# RF_DAC.net
KiCad netlist of a schematic drawn in Altium Designer
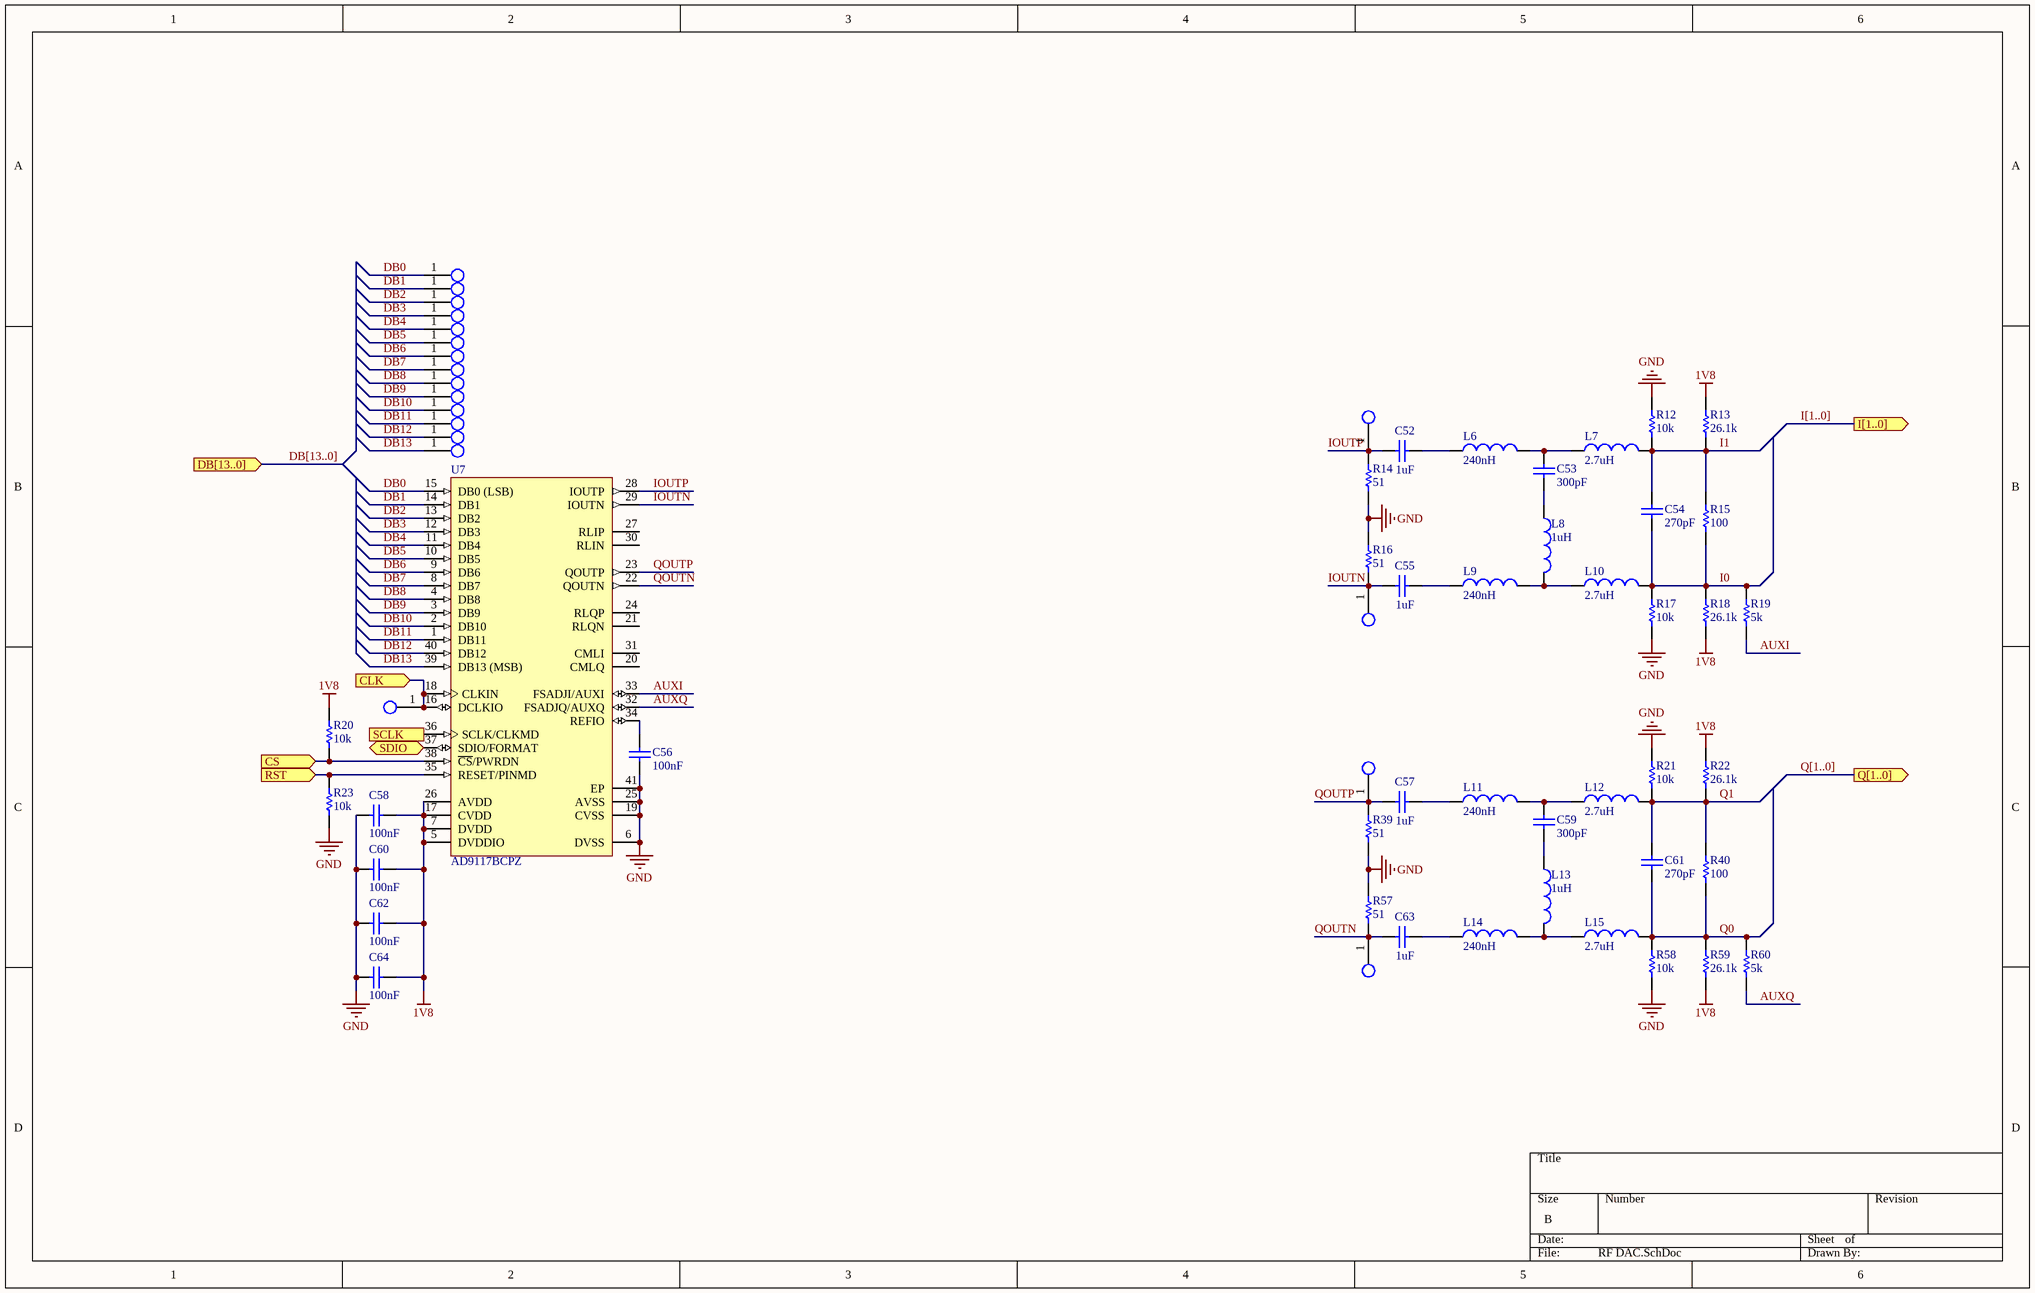
[diagram p0: RF DAC.SchDoc]

(export (version "E")
  (design (tool "Eeschema 10.0.6"))
  (components
    (comp (ref "C52")
      (value "1uF")
      (footprint "1608[0603]")
      (description "Capacitor")
      (fields (field (name "Comment") "Cap") (field (name "PUBLISHER") "Altium Limited"))
      (libsource (lib "Miscellaneous Devices") (part "Cap"))
    )
    (comp (ref "C53")
      (value "300pF")
      (footprint "0402-A")
      (description "Capacitor")
      (fields (field (name "Comment") "Cap") (field (name "PUBLISHER") "Altium Limited"))
      (libsource (lib "Miscellaneous Devices") (part "Cap"))
    )
    (comp (ref "C54")
      (value "270pF")
      (footprint "0402-A")
      (description "Capacitor")
      (fields (field (name "Comment") "Cap") (field (name "PUBLISHER") "Altium Limited"))
      (libsource (lib "Miscellaneous Devices") (part "Cap"))
    )
    (comp (ref "C55")
      (value "1uF")
      (footprint "1608[0603]")
      (description "Capacitor")
      (fields (field (name "Comment") "Cap") (field (name "PUBLISHER") "Altium Limited"))
      (libsource (lib "Miscellaneous Devices") (part "Cap"))
    )
    (comp (ref "C56")
      (value "100nF")
      (footprint "0402-A")
      (description "Capacitor")
      (fields (field (name "Comment") "Cap") (field (name "PUBLISHER") "Altium Limited"))
      (libsource (lib "Miscellaneous Devices") (part "Cap"))
    )
    (comp (ref "C57")
      (value "1uF")
      (footprint "1608[0603]")
      (description "Capacitor")
      (fields (field (name "Comment") "Cap") (field (name "PUBLISHER") "Altium Limited"))
      (libsource (lib "Miscellaneous Devices") (part "Cap"))
    )
    (comp (ref "C58")
      (value "100nF")
      (footprint "0402-A")
      (description "Capacitor")
      (fields (field (name "Comment") "Cap") (field (name "PUBLISHER") "Altium Limited"))
      (libsource (lib "Miscellaneous Devices") (part "Cap"))
    )
    (comp (ref "C59")
      (value "300pF")
      (footprint "0402-A")
      (description "Capacitor")
      (fields (field (name "Comment") "Cap") (field (name "PUBLISHER") "Altium Limited"))
      (libsource (lib "Miscellaneous Devices") (part "Cap"))
    )
    (comp (ref "C60")
      (value "100nF")
      (footprint "0402-A")
      (description "Capacitor")
      (fields (field (name "Comment") "Cap") (field (name "PUBLISHER") "Altium Limited"))
      (libsource (lib "Miscellaneous Devices") (part "Cap"))
    )
    (comp (ref "C61")
      (value "270pF")
      (footprint "0402-A")
      (description "Capacitor")
      (fields (field (name "Comment") "Cap") (field (name "PUBLISHER") "Altium Limited"))
      (libsource (lib "Miscellaneous Devices") (part "Cap"))
    )
    (comp (ref "C62")
      (value "100nF")
      (footprint "0402-A")
      (description "Capacitor")
      (fields (field (name "Comment") "Cap") (field (name "PUBLISHER") "Altium Limited"))
      (libsource (lib "Miscellaneous Devices") (part "Cap"))
    )
    (comp (ref "C63")
      (value "1uF")
      (footprint "1608[0603]")
      (description "Capacitor")
      (fields (field (name "Comment") "Cap") (field (name "PUBLISHER") "Altium Limited"))
      (libsource (lib "Miscellaneous Devices") (part "Cap"))
    )
    (comp (ref "C64")
      (value "100nF")
      (footprint "0402-A")
      (description "Capacitor")
      (fields (field (name "Comment") "Cap") (field (name "PUBLISHER") "Altium Limited"))
      (libsource (lib "Miscellaneous Devices") (part "Cap"))
    )
    (comp (ref "CLK")
      (value "5029")
      (footprint "EXPOSED PAD 0.02X0.02")
      (libsource (lib "5029") (part "5029"))
    )
    (comp (ref "DB0")
      (value "5029")
      (footprint "EXPOSED PAD 0.02X0.02")
      (libsource (lib "5029") (part "5029"))
    )
    (comp (ref "DB1")
      (value "5029")
      (footprint "EXPOSED PAD 0.02X0.02")
      (libsource (lib "5029") (part "5029"))
    )
    (comp (ref "DB2")
      (value "5029")
      (footprint "EXPOSED PAD 0.02X0.02")
      (libsource (lib "5029") (part "5029"))
    )
    (comp (ref "DB3")
      (value "5029")
      (footprint "EXPOSED PAD 0.02X0.02")
      (libsource (lib "5029") (part "5029"))
    )
    (comp (ref "DB4")
      (value "5029")
      (footprint "EXPOSED PAD 0.02X0.02")
      (libsource (lib "5029") (part "5029"))
    )
    (comp (ref "DB5")
      (value "5029")
      (footprint "EXPOSED PAD 0.02X0.02")
      (libsource (lib "5029") (part "5029"))
    )
    (comp (ref "DB6")
      (value "5029")
      (footprint "EXPOSED PAD 0.02X0.02")
      (libsource (lib "5029") (part "5029"))
    )
    (comp (ref "DB7")
      (value "5029")
      (footprint "EXPOSED PAD 0.02X0.02")
      (libsource (lib "5029") (part "5029"))
    )
    (comp (ref "DB8")
      (value "5029")
      (footprint "EXPOSED PAD 0.02X0.02")
      (libsource (lib "5029") (part "5029"))
    )
    (comp (ref "DB9")
      (value "5029")
      (footprint "EXPOSED PAD 0.02X0.02")
      (libsource (lib "5029") (part "5029"))
    )
    (comp (ref "DB10")
      (value "5029")
      (footprint "EXPOSED PAD 0.02X0.02")
      (libsource (lib "5029") (part "5029"))
    )
    (comp (ref "DB11")
      (value "5029")
      (footprint "EXPOSED PAD 0.02X0.02")
      (libsource (lib "5029") (part "5029"))
    )
    (comp (ref "DB12")
      (value "5029")
      (footprint "EXPOSED PAD 0.02X0.02")
      (libsource (lib "5029") (part "5029"))
    )
    (comp (ref "DB13")
      (value "5029")
      (footprint "EXPOSED PAD 0.02X0.02")
      (libsource (lib "5029") (part "5029"))
    )
    (comp (ref "J22")
      (value "5029")
      (footprint "EXPOSED PAD 0.02X0.02")
      (libsource (lib "5029") (part "5029"))
    )
    (comp (ref "J25")
      (value "5029")
      (footprint "EXPOSED PAD 0.02X0.02")
      (libsource (lib "5029") (part "5029"))
    )
    (comp (ref "J26")
      (value "5029")
      (footprint "EXPOSED PAD 0.02X0.02")
      (libsource (lib "5029") (part "5029"))
    )
    (comp (ref "J29")
      (value "5029")
      (footprint "EXPOSED PAD 0.02X0.02")
      (libsource (lib "5029") (part "5029"))
    )
    (comp (ref "L6")
      (value "240nH")
      (footprint "0402-A")
      (description "Inductor")
      (fields (field (name "PUBLISHER") "Altium Limited"))
      (libsource (lib "Miscellaneous Devices") (part "Inductor"))
    )
    (comp (ref "L7")
      (value "2.7uH")
      (footprint "1608[0603]")
      (description "Inductor")
      (fields (field (name "PUBLISHER") "Altium Limited"))
      (libsource (lib "Miscellaneous Devices") (part "Inductor"))
    )
    (comp (ref "L8")
      (value "1uH")
      (footprint "1608[0603]")
      (description "Inductor")
      (fields (field (name "PUBLISHER") "Altium Limited"))
      (libsource (lib "Miscellaneous Devices") (part "Inductor"))
    )
    (comp (ref "L9")
      (value "240nH")
      (footprint "0402-A")
      (description "Inductor")
      (fields (field (name "PUBLISHER") "Altium Limited"))
      (libsource (lib "Miscellaneous Devices") (part "Inductor"))
    )
    (comp (ref "L10")
      (value "2.7uH")
      (footprint "1608[0603]")
      (description "Inductor")
      (fields (field (name "PUBLISHER") "Altium Limited"))
      (libsource (lib "Miscellaneous Devices") (part "Inductor"))
    )
    (comp (ref "L11")
      (value "240nH")
      (footprint "0402-A")
      (description "Inductor")
      (fields (field (name "PUBLISHER") "Altium Limited"))
      (libsource (lib "Miscellaneous Devices") (part "Inductor"))
    )
    (comp (ref "L12")
      (value "2.7uH")
      (footprint "1608[0603]")
      (description "Inductor")
      (fields (field (name "PUBLISHER") "Altium Limited"))
      (libsource (lib "Miscellaneous Devices") (part "Inductor"))
    )
    (comp (ref "L13")
      (value "1uH")
      (footprint "1608[0603]")
      (description "Inductor")
      (fields (field (name "PUBLISHER") "Altium Limited"))
      (libsource (lib "Miscellaneous Devices") (part "Inductor"))
    )
    (comp (ref "L14")
      (value "240nH")
      (footprint "0402-A")
      (description "Inductor")
      (fields (field (name "PUBLISHER") "Altium Limited"))
      (libsource (lib "Miscellaneous Devices") (part "Inductor"))
    )
    (comp (ref "L15")
      (value "2.7uH")
      (footprint "1608[0603]")
      (description "Inductor")
      (fields (field (name "PUBLISHER") "Altium Limited"))
      (libsource (lib "Miscellaneous Devices") (part "Inductor"))
    )
    (comp (ref "R12")
      (value "10k")
      (footprint "0402-A")
      (description "Resistor")
      (fields (field (name "Comment") "Res1") (field (name "PUBLISHER") "Altium Limited"))
      (libsource (lib "Miscellaneous Devices") (part "Res1"))
    )
    (comp (ref "R13")
      (value "26.1k")
      (footprint "0402-A")
      (description "Resistor")
      (fields (field (name "Comment") "Res1") (field (name "PUBLISHER") "Altium Limited"))
      (libsource (lib "Miscellaneous Devices") (part "Res1"))
    )
    (comp (ref "R14")
      (value "51")
      (footprint "0402-A")
      (description "Resistor")
      (fields (field (name "Comment") "Res1") (field (name "PUBLISHER") "Altium Limited"))
      (libsource (lib "Miscellaneous Devices") (part "Res1"))
    )
    (comp (ref "R15")
      (value "100")
      (footprint "0402-A")
      (description "Resistor")
      (fields (field (name "Comment") "Res1") (field (name "PUBLISHER") "Altium Limited"))
      (libsource (lib "Miscellaneous Devices") (part "Res1"))
    )
    (comp (ref "R16")
      (value "51")
      (footprint "0402-A")
      (description "Resistor")
      (fields (field (name "Comment") "Res1") (field (name "PUBLISHER") "Altium Limited"))
      (libsource (lib "Miscellaneous Devices") (part "Res1"))
    )
    (comp (ref "R17")
      (value "10k")
      (footprint "0402-A")
      (description "Resistor")
      (fields (field (name "Comment") "Res1") (field (name "PUBLISHER") "Altium Limited"))
      (libsource (lib "Miscellaneous Devices") (part "Res1"))
    )
    (comp (ref "R18")
      (value "26.1k")
      (footprint "0402-A")
      (description "Resistor")
      (fields (field (name "Comment") "Res1") (field (name "PUBLISHER") "Altium Limited"))
      (libsource (lib "Miscellaneous Devices") (part "Res1"))
    )
    (comp (ref "R19")
      (value "5k")
      (footprint "0402-A")
      (description "Resistor")
      (fields (field (name "Comment") "Res1") (field (name "PUBLISHER") "Altium Limited"))
      (libsource (lib "Miscellaneous Devices") (part "Res1"))
    )
    (comp (ref "R20")
      (value "10k")
      (footprint "0402-A")
      (description "Resistor")
      (fields (field (name "Comment") "Res1") (field (name "PUBLISHER") "Altium Limited"))
      (libsource (lib "Miscellaneous Devices") (part "Res1"))
    )
    (comp (ref "R21")
      (value "10k")
      (footprint "0402-A")
      (description "Resistor")
      (fields (field (name "Comment") "Res1") (field (name "PUBLISHER") "Altium Limited"))
      (libsource (lib "Miscellaneous Devices") (part "Res1"))
    )
    (comp (ref "R22")
      (value "26.1k")
      (footprint "0402-A")
      (description "Resistor")
      (fields (field (name "Comment") "Res1") (field (name "PUBLISHER") "Altium Limited"))
      (libsource (lib "Miscellaneous Devices") (part "Res1"))
    )
    (comp (ref "R23")
      (value "10k")
      (footprint "0402-A")
      (description "Resistor")
      (fields (field (name "Comment") "Res1") (field (name "PUBLISHER") "Altium Limited"))
      (libsource (lib "Miscellaneous Devices") (part "Res1"))
    )
    (comp (ref "R39")
      (value "51")
      (footprint "0402-A")
      (description "Resistor")
      (fields (field (name "Comment") "Res1") (field (name "PUBLISHER") "Altium Limited"))
      (libsource (lib "Miscellaneous Devices") (part "Res1"))
    )
    (comp (ref "R40")
      (value "100")
      (footprint "0402-A")
      (description "Resistor")
      (fields (field (name "Comment") "Res1") (field (name "PUBLISHER") "Altium Limited"))
      (libsource (lib "Miscellaneous Devices") (part "Res1"))
    )
    (comp (ref "R57")
      (value "51")
      (footprint "0402-A")
      (description "Resistor")
      (fields (field (name "Comment") "Res1") (field (name "PUBLISHER") "Altium Limited"))
      (libsource (lib "Miscellaneous Devices") (part "Res1"))
    )
    (comp (ref "R58")
      (value "10k")
      (footprint "0402-A")
      (description "Resistor")
      (fields (field (name "Comment") "Res1") (field (name "PUBLISHER") "Altium Limited"))
      (libsource (lib "Miscellaneous Devices") (part "Res1"))
    )
    (comp (ref "R59")
      (value "26.1k")
      (footprint "0402-A")
      (description "Resistor")
      (fields (field (name "Comment") "Res1") (field (name "PUBLISHER") "Altium Limited"))
      (libsource (lib "Miscellaneous Devices") (part "Res1"))
    )
    (comp (ref "R60")
      (value "5k")
      (footprint "0402-A")
      (description "Resistor")
      (fields (field (name "Comment") "Res1") (field (name "PUBLISHER") "Altium Limited"))
      (libsource (lib "Miscellaneous Devices") (part "Res1"))
    )
    (comp (ref "U7")
      (value "AD9117BCPZ")
      (footprint "CP-40-1_N")
      (description "Dual 14-Bit Low Power TxDAC Digital-to-Analog Converter, 0 to +70 degC, CP-40-1, Pb-Free, Tray")
      (fields (field (name "MANUFACTURER") "Analog Devices") (field (name "GENERIC PART NUMBER") "AD9117"))
      (libsource (lib "Altium Content Vault") (part "ADI-AD9117-CP-40-1"))
    )
  )
  (nets
    (net (code "1") (name "/AUXI") (class "Default")
      (node (ref "R19") (pin "1") (pinfunction "1_1") (pintype "passive"))
      (node (ref "U7") (pin "33") (pinfunction "FSADJI/AUXI_33") (pintype "bidirectional"))
    )
    (net (code "2") (name "/AUXQ") (class "Default")
      (node (ref "R60") (pin "1") (pinfunction "1_1") (pintype "passive"))
      (node (ref "U7") (pin "32") (pinfunction "FSADJQ/AUXQ_32") (pintype "bidirectional"))
    )
    (net (code "3") (name "/CLK") (class "Default")
      (node (ref "CLK") (pin "1") (pintype "passive"))
      (node (ref "U7") (pin "16") (pinfunction "DCLKIO_16") (pintype "bidirectional"))
      (node (ref "U7") (pin "18") (pinfunction "CLKIN_18") (pintype "input"))
    )
    (net (code "4") (name "/CS") (class "Default")
      (node (ref "R20") (pin "1") (pinfunction "1_1") (pintype "passive"))
      (node (ref "U7") (pin "38") (pinfunction "~{CS}/PWRDN_38") (pintype "input"))
    )
    (net (code "5") (name "/DB0") (class "Default")
      (node (ref "DB0") (pin "1") (pintype "passive"))
      (node (ref "U7") (pin "15") (pinfunction "DB0_(LSB)_15") (pintype "input"))
    )
    (net (code "6") (name "/DB1") (class "Default")
      (node (ref "DB1") (pin "1") (pintype "passive"))
      (node (ref "U7") (pin "14") (pinfunction "DB1_14") (pintype "input"))
    )
    (net (code "7") (name "/DB2") (class "Default")
      (node (ref "DB2") (pin "1") (pintype "passive"))
      (node (ref "U7") (pin "13") (pinfunction "DB2_13") (pintype "input"))
    )
    (net (code "8") (name "/DB3") (class "Default")
      (node (ref "DB3") (pin "1") (pintype "passive"))
      (node (ref "U7") (pin "12") (pinfunction "DB3_12") (pintype "input"))
    )
    (net (code "9") (name "/DB4") (class "Default")
      (node (ref "DB4") (pin "1") (pintype "passive"))
      (node (ref "U7") (pin "11") (pinfunction "DB4_11") (pintype "input"))
    )
    (net (code "10") (name "/DB5") (class "Default")
      (node (ref "DB5") (pin "1") (pintype "passive"))
      (node (ref "U7") (pin "10") (pinfunction "DB5_10") (pintype "input"))
    )
    (net (code "11") (name "/DB6") (class "Default")
      (node (ref "DB6") (pin "1") (pintype "passive"))
      (node (ref "U7") (pin "9") (pinfunction "DB6_9") (pintype "input"))
    )
    (net (code "12") (name "/DB7") (class "Default")
      (node (ref "DB7") (pin "1") (pintype "passive"))
      (node (ref "U7") (pin "8") (pinfunction "DB7_8") (pintype "input"))
    )
    (net (code "13") (name "/DB8") (class "Default")
      (node (ref "DB8") (pin "1") (pintype "passive"))
      (node (ref "U7") (pin "4") (pinfunction "DB8_4") (pintype "input"))
    )
    (net (code "14") (name "/DB9") (class "Default")
      (node (ref "DB9") (pin "1") (pintype "passive"))
      (node (ref "U7") (pin "3") (pinfunction "DB9_3") (pintype "input"))
    )
    (net (code "15") (name "/DB10") (class "Default")
      (node (ref "DB10") (pin "1") (pintype "passive"))
      (node (ref "U7") (pin "2") (pinfunction "DB10_2") (pintype "input"))
    )
    (net (code "16") (name "/DB11") (class "Default")
      (node (ref "DB11") (pin "1") (pintype "passive"))
      (node (ref "U7") (pin "1") (pinfunction "DB11_1") (pintype "input"))
    )
    (net (code "17") (name "/DB12") (class "Default")
      (node (ref "DB12") (pin "1") (pintype "passive"))
      (node (ref "U7") (pin "40") (pinfunction "DB12_40") (pintype "input"))
    )
    (net (code "18") (name "/DB13") (class "Default")
      (node (ref "DB13") (pin "1") (pintype "passive"))
      (node (ref "U7") (pin "39") (pinfunction "DB13_(MSB)_39") (pintype "input"))
    )
    (net (code "20") (name "/I0") (class "Default")
      (node (ref "C54") (pin "2") (pinfunction "2_2") (pintype "passive"))
      (node (ref "L10") (pin "2") (pinfunction "2_2") (pintype "passive"))
      (node (ref "R15") (pin "1") (pinfunction "1_1") (pintype "passive"))
      (node (ref "R17") (pin "2") (pinfunction "2_2") (pintype "passive"))
      (node (ref "R18") (pin "2") (pinfunction "2_2") (pintype "passive"))
      (node (ref "R19") (pin "2") (pinfunction "2_2") (pintype "passive"))
    )
    (net (code "21") (name "/I1") (class "Default")
      (node (ref "C54") (pin "1") (pinfunction "1_1") (pintype "passive"))
      (node (ref "L7") (pin "2") (pinfunction "2_2") (pintype "passive"))
      (node (ref "R12") (pin "1") (pinfunction "1_1") (pintype "passive"))
      (node (ref "R13") (pin "1") (pinfunction "1_1") (pintype "passive"))
      (node (ref "R15") (pin "2") (pinfunction "2_2") (pintype "passive"))
    )
    (net (code "22") (name "/IOUTN") (class "Default")
      (node (ref "C55") (pin "2") (pinfunction "2_2") (pintype "passive"))
      (node (ref "J25") (pin "1") (pintype "passive"))
      (node (ref "R16") (pin "1") (pinfunction "1_1") (pintype "passive"))
      (node (ref "U7") (pin "29") (pinfunction "IOUTN_29") (pintype "output"))
    )
    (net (code "23") (name "/IOUTP") (class "Default")
      (node (ref "C52") (pin "2") (pinfunction "2_2") (pintype "passive"))
      (node (ref "J22") (pin "1") (pintype "passive"))
      (node (ref "R14") (pin "2") (pinfunction "2_2") (pintype "passive"))
      (node (ref "U7") (pin "28") (pinfunction "IOUTP_28") (pintype "output"))
    )
    (net (code "25") (name "/Q0") (class "Default")
      (node (ref "C61") (pin "2") (pinfunction "2_2") (pintype "passive"))
      (node (ref "L15") (pin "2") (pinfunction "2_2") (pintype "passive"))
      (node (ref "R40") (pin "1") (pinfunction "1_1") (pintype "passive"))
      (node (ref "R58") (pin "2") (pinfunction "2_2") (pintype "passive"))
      (node (ref "R59") (pin "2") (pinfunction "2_2") (pintype "passive"))
      (node (ref "R60") (pin "2") (pinfunction "2_2") (pintype "passive"))
    )
    (net (code "26") (name "/Q1") (class "Default")
      (node (ref "C61") (pin "1") (pinfunction "1_1") (pintype "passive"))
      (node (ref "L12") (pin "2") (pinfunction "2_2") (pintype "passive"))
      (node (ref "R21") (pin "1") (pinfunction "1_1") (pintype "passive"))
      (node (ref "R22") (pin "1") (pinfunction "1_1") (pintype "passive"))
      (node (ref "R40") (pin "2") (pinfunction "2_2") (pintype "passive"))
    )
    (net (code "27") (name "/QOUTN") (class "Default")
      (node (ref "C63") (pin "2") (pinfunction "2_2") (pintype "passive"))
      (node (ref "J29") (pin "1") (pintype "passive"))
      (node (ref "R57") (pin "1") (pinfunction "1_1") (pintype "passive"))
      (node (ref "U7") (pin "22") (pinfunction "QOUTN_22") (pintype "output"))
    )
    (net (code "28") (name "/QOUTP") (class "Default")
      (node (ref "C57") (pin "2") (pinfunction "2_2") (pintype "passive"))
      (node (ref "J26") (pin "1") (pintype "passive"))
      (node (ref "R39") (pin "2") (pinfunction "2_2") (pintype "passive"))
      (node (ref "U7") (pin "23") (pinfunction "QOUTP_23") (pintype "output"))
    )
    (net (code "30") (name "/RST") (class "Default")
      (node (ref "R23") (pin "2") (pinfunction "2_2") (pintype "passive"))
      (node (ref "U7") (pin "35") (pinfunction "RESET/PINMD_35") (pintype "input"))
    )
    (net (code "31") (name "/SCLK") (class "Default")
      (node (ref "U7") (pin "36") (pinfunction "SCLK/CLKMD_36") (pintype "input"))
    )
    (net (code "32") (name "/SDIO") (class "Default")
      (node (ref "U7") (pin "37") (pinfunction "SDIO/FORMAT_37") (pintype "bidirectional"))
    )
    (net (code "33") (name "1V8") (class "Default")
      (node (ref "C58") (pin "2") (pinfunction "2_2") (pintype "passive"))
      (node (ref "C60") (pin "2") (pinfunction "2_2") (pintype "passive"))
      (node (ref "C62") (pin "2") (pinfunction "2_2") (pintype "passive"))
      (node (ref "C64") (pin "2") (pinfunction "2_2") (pintype "passive"))
      (node (ref "R13") (pin "2") (pinfunction "2_2") (pintype "passive"))
      (node (ref "R18") (pin "1") (pinfunction "1_1") (pintype "passive"))
      (node (ref "R20") (pin "2") (pinfunction "2_2") (pintype "passive"))
      (node (ref "R22") (pin "2") (pinfunction "2_2") (pintype "passive"))
      (node (ref "R59") (pin "1") (pinfunction "1_1") (pintype "passive"))
      (node (ref "U7") (pin "17") (pinfunction "CVDD_17") (pintype "power_in"))
      (node (ref "U7") (pin "26") (pinfunction "AVDD_26") (pintype "power_in"))
      (node (ref "U7") (pin "5") (pinfunction "DVDDIO_5") (pintype "power_in"))
      (node (ref "U7") (pin "7") (pinfunction "DVDD_7") (pintype "power_in"))
    )
    (net (code "34") (name "GND") (class "Default")
      (node (ref "C56") (pin "1") (pinfunction "1_1") (pintype "passive"))
      (node (ref "C58") (pin "1") (pinfunction "1_1") (pintype "passive"))
      (node (ref "C60") (pin "1") (pinfunction "1_1") (pintype "passive"))
      (node (ref "C62") (pin "1") (pinfunction "1_1") (pintype "passive"))
      (node (ref "C64") (pin "1") (pinfunction "1_1") (pintype "passive"))
      (node (ref "R12") (pin "2") (pinfunction "2_2") (pintype "passive"))
      (node (ref "R14") (pin "1") (pinfunction "1_1") (pintype "passive"))
      (node (ref "R16") (pin "2") (pinfunction "2_2") (pintype "passive"))
      (node (ref "R17") (pin "1") (pinfunction "1_1") (pintype "passive"))
      (node (ref "R21") (pin "2") (pinfunction "2_2") (pintype "passive"))
      (node (ref "R23") (pin "1") (pinfunction "1_1") (pintype "passive"))
      (node (ref "R39") (pin "1") (pinfunction "1_1") (pintype "passive"))
      (node (ref "R57") (pin "2") (pinfunction "2_2") (pintype "passive"))
      (node (ref "R58") (pin "1") (pinfunction "1_1") (pintype "passive"))
      (node (ref "U7") (pin "19") (pinfunction "CVSS_19") (pintype "power_in"))
      (node (ref "U7") (pin "25") (pinfunction "AVSS_25") (pintype "power_in"))
      (node (ref "U7") (pin "41") (pinfunction "EP_41") (pintype "power_in"))
      (node (ref "U7") (pin "6") (pinfunction "DVSS_6") (pintype "power_in"))
    )
    (net (code "35") (name "Net-(C52-Pad1)") (class "Default")
      (node (ref "C52") (pin "1") (pinfunction "1_1") (pintype "passive"))
      (node (ref "L6") (pin "1") (pinfunction "1_1") (pintype "passive"))
    )
    (net (code "36") (name "Net-(C53-Pad1)") (class "Default")
      (node (ref "C53") (pin "1") (pinfunction "1_1") (pintype "passive"))
      (node (ref "L6") (pin "2") (pinfunction "2_2") (pintype "passive"))
      (node (ref "L7") (pin "1") (pinfunction "1_1") (pintype "passive"))
    )
    (net (code "37") (name "Net-(C53-Pad2)") (class "Default")
      (node (ref "C53") (pin "2") (pinfunction "2_2") (pintype "passive"))
      (node (ref "L8") (pin "1") (pinfunction "1_1") (pintype "passive"))
    )
    (net (code "38") (name "Net-(C55-Pad1)") (class "Default")
      (node (ref "C55") (pin "1") (pinfunction "1_1") (pintype "passive"))
      (node (ref "L9") (pin "1") (pinfunction "1_1") (pintype "passive"))
    )
    (net (code "39") (name "Net-(C57-Pad1)") (class "Default")
      (node (ref "C57") (pin "1") (pinfunction "1_1") (pintype "passive"))
      (node (ref "L11") (pin "1") (pinfunction "1_1") (pintype "passive"))
    )
    (net (code "40") (name "Net-(C59-Pad1)") (class "Default")
      (node (ref "C59") (pin "1") (pinfunction "1_1") (pintype "passive"))
      (node (ref "L11") (pin "2") (pinfunction "2_2") (pintype "passive"))
      (node (ref "L12") (pin "1") (pinfunction "1_1") (pintype "passive"))
    )
    (net (code "41") (name "Net-(C59-Pad2)") (class "Default")
      (node (ref "C59") (pin "2") (pinfunction "2_2") (pintype "passive"))
      (node (ref "L13") (pin "1") (pinfunction "1_1") (pintype "passive"))
    )
    (net (code "42") (name "Net-(C63-Pad1)") (class "Default")
      (node (ref "C63") (pin "1") (pinfunction "1_1") (pintype "passive"))
      (node (ref "L14") (pin "1") (pinfunction "1_1") (pintype "passive"))
    )
    (net (code "43") (name "Net-(L10-Pad1)") (class "Default")
      (node (ref "L10") (pin "1") (pinfunction "1_1") (pintype "passive"))
      (node (ref "L8") (pin "2") (pinfunction "2_2") (pintype "passive"))
      (node (ref "L9") (pin "2") (pinfunction "2_2") (pintype "passive"))
    )
    (net (code "44") (name "Net-(L13-Pad2)") (class "Default")
      (node (ref "L13") (pin "2") (pinfunction "2_2") (pintype "passive"))
      (node (ref "L14") (pin "2") (pinfunction "2_2") (pintype "passive"))
      (node (ref "L15") (pin "1") (pinfunction "1_1") (pintype "passive"))
    )
    (net (code "45") (name "Net-(U7-REFIO)") (class "Default")
      (node (ref "C56") (pin "2") (pinfunction "2_2") (pintype "passive"))
      (node (ref "U7") (pin "34") (pinfunction "REFIO_34") (pintype "bidirectional"))
    )
    (net (code "46") (name "unconnected-(U7-CMLI-Pad31)") (class "Default")
      (node (ref "U7") (pin "31") (pinfunction "CMLI_31") (pintype "passive"))
    )
    (net (code "47") (name "unconnected-(U7-CMLQ-Pad20)") (class "Default")
      (node (ref "U7") (pin "20") (pinfunction "CMLQ_20") (pintype "passive"))
    )
    (net (code "48") (name "unconnected-(U7-RLIN-Pad30)") (class "Default")
      (node (ref "U7") (pin "30") (pinfunction "RLIN_30") (pintype "passive"))
    )
    (net (code "49") (name "unconnected-(U7-RLIP-Pad27)") (class "Default")
      (node (ref "U7") (pin "27") (pinfunction "RLIP_27") (pintype "passive"))
    )
    (net (code "50") (name "unconnected-(U7-RLQN-Pad21)") (class "Default")
      (node (ref "U7") (pin "21") (pinfunction "RLQN_21") (pintype "passive"))
    )
    (net (code "51") (name "unconnected-(U7-RLQP-Pad24)") (class "Default")
      (node (ref "U7") (pin "24") (pinfunction "RLQP_24") (pintype "passive"))
    )
  )
)
